# HBridge.net
KiCad netlist of a schematic drawn in Altium Designer
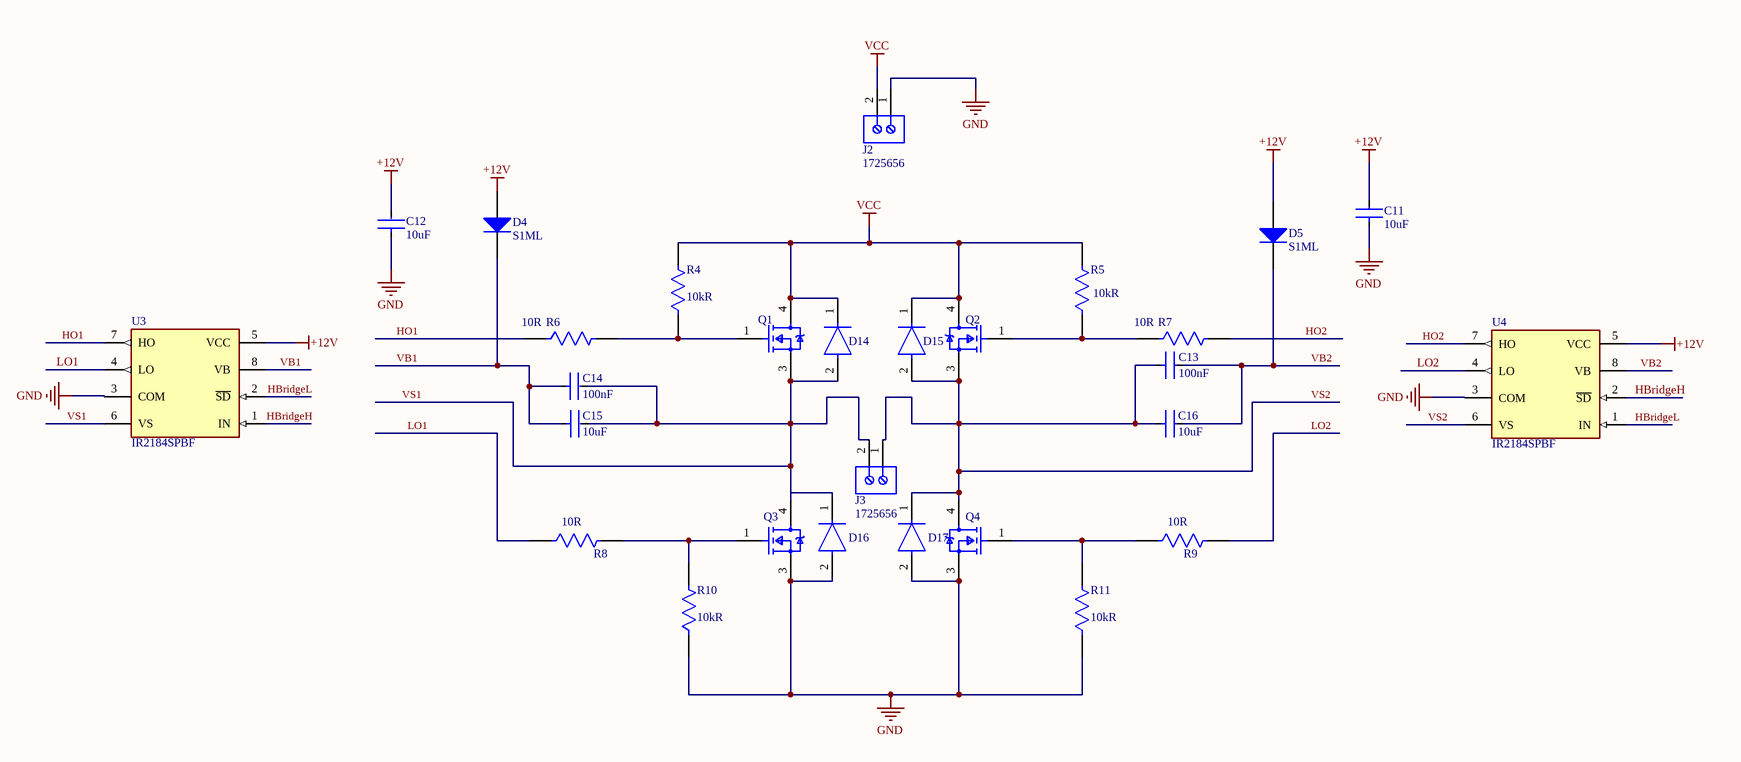
[diagram p0: HBridge.SchDoc]

(export (version "E")
  (design (tool "Eeschema 10.0.6"))
  (components
    (comp (ref "C11")
      (value "CL21A106KOQNNNE")
      (footprint "FP-CL21-IPC_B")
      (description "CL21 Series 0805 10uF 16V ±10% Tolerance X5R Multilayer Ceramic Chip Capacitor")
      (fields
        (field (name "VOLTAGE") "16V")
        (field (name "CAPACITANCE") "10uF")
        (field (name "TOLERANCE") "10%")
      )
      (libsource (lib "Altium Content Vault") (part "b4654b650e69147ec39a6b967a45e02"))
    )
    (comp (ref "C12")
      (value "CL21A106KOQNNNE")
      (footprint "FP-CL21-IPC_B")
      (description "CL21 Series 0805 10uF 16V ±10% Tolerance X5R Multilayer Ceramic Chip Capacitor")
      (fields
        (field (name "VOLTAGE") "16V")
        (field (name "CAPACITANCE") "10uF")
        (field (name "TOLERANCE") "10%")
      )
      (libsource (lib "Altium Content Vault") (part "b4654b650e69147ec39a6b967a45e02"))
    )
    (comp (ref "C13")
      (value "CL21B104KBCNNNC")
      (footprint "FP-CL21-IPC_C")
      (description "CL21 Series 0805 100nF 50V ±10% Tolerance X7R Multilayer Ceramic Chip Capacitor")
      (fields
        (field (name "TOLERANCE") "10%")
        (field (name "CAPACITANCE") "100nF")
        (field (name "VOLTAGE") "50V")
      )
      (libsource (lib "Altium Content Vault") (part "b4654b650e69147ec39a6b967a45e02"))
    )
    (comp (ref "C14")
      (value "CL21B104KBCNNNC")
      (footprint "FP-CL21-IPC_C")
      (description "CL21 Series 0805 100nF 50V ±10% Tolerance X7R Multilayer Ceramic Chip Capacitor")
      (fields
        (field (name "TOLERANCE") "10%")
        (field (name "CAPACITANCE") "100nF")
        (field (name "VOLTAGE") "50V")
      )
      (libsource (lib "Altium Content Vault") (part "b4654b650e69147ec39a6b967a45e02"))
    )
    (comp (ref "C15")
      (value "CL21A106KOQNNNE")
      (footprint "FP-CL21-IPC_B")
      (description "CL21 Series 0805 10uF 16V ±10% Tolerance X5R Multilayer Ceramic Chip Capacitor")
      (fields
        (field (name "VOLTAGE") "16V")
        (field (name "CAPACITANCE") "10uF")
        (field (name "TOLERANCE") "10%")
      )
      (libsource (lib "Altium Content Vault") (part "b4654b650e69147ec39a6b967a45e02"))
    )
    (comp (ref "C16")
      (value "CL21A106KOQNNNE")
      (footprint "FP-CL21-IPC_B")
      (description "CL21 Series 0805 10uF 16V ±10% Tolerance X5R Multilayer Ceramic Chip Capacitor")
      (fields
        (field (name "VOLTAGE") "16V")
        (field (name "CAPACITANCE") "10uF")
        (field (name "TOLERANCE") "10%")
      )
      (libsource (lib "Altium Content Vault") (part "b4654b650e69147ec39a6b967a45e02"))
    )
    (comp (ref "D4")
      (value "S1ML")
      (footprint "TWS-S1ML_V")
      (description "Rectifier, 1 A, 1.1 V, -55 to 175 degC, 2-Pin SMD, RoHS, Tape and Reel")
      (fields (field (name "MANUFACTURER") "Taiwan Semiconductor"))
      (libsource (lib "Altium Content Vault") (part "D-AK-2"))
    )
    (comp (ref "D5")
      (value "S1ML")
      (footprint "TWS-S1ML_V")
      (description "Rectifier, 1 A, 1.1 V, -55 to 175 degC, 2-Pin SMD, RoHS, Tape and Reel")
      (fields (field (name "MANUFACTURER") "Taiwan Semiconductor"))
      (libsource (lib "Altium Content Vault") (part "D-AK-2"))
    )
    (comp (ref "D14")
      (value "1N4148WQ-7-F")
      (footprint "FP-SOD123-MFG")
      (description "DIODE GEN PURP 100V 300MA SOD123")
      (fields
        (field (name "MANUFACTURER") "Diodes Inc.")
        (field (name "OCTOPART") "https://octopart.com/1n4148wq-7-f-diodes+inc.-34965875")
      )
      (libsource (lib "Altium Content Vault") (part "d7152d700b627762746794eb795d46e"))
    )
    (comp (ref "D15")
      (value "1N4148WQ-7-F")
      (footprint "FP-SOD123-MFG")
      (description "DIODE GEN PURP 100V 300MA SOD123")
      (fields
        (field (name "MANUFACTURER") "Diodes Inc.")
        (field (name "OCTOPART") "https://octopart.com/1n4148wq-7-f-diodes+inc.-34965875")
      )
      (libsource (lib "Altium Content Vault") (part "d7152d700b627762746794eb795d46e"))
    )
    (comp (ref "D16")
      (value "1N4148WQ-7-F")
      (footprint "FP-SOD123-MFG")
      (description "DIODE GEN PURP 100V 300MA SOD123")
      (fields
        (field (name "MANUFACTURER") "Diodes Inc.")
        (field (name "OCTOPART") "https://octopart.com/1n4148wq-7-f-diodes+inc.-34965875")
      )
      (libsource (lib "Altium Content Vault") (part "d7152d700b627762746794eb795d46e"))
    )
    (comp (ref "D17")
      (value "1N4148WQ-7-F")
      (footprint "FP-SOD123-MFG")
      (description "DIODE GEN PURP 100V 300MA SOD123")
      (fields
        (field (name "MANUFACTURER") "Diodes Inc.")
        (field (name "OCTOPART") "https://octopart.com/1n4148wq-7-f-diodes+inc.-34965875")
      )
      (libsource (lib "Altium Content Vault") (part "d7152d700b627762746794eb795d46e"))
    )
    (comp (ref "J2")
      (value "1725656")
      (footprint "PHOE-1725656-2")
      (description "Male Header, Pitch 2.54 mm, 1 x 2 Position, Height 9 mm, Tail Length 3.5 mm")
      (fields (field (name "MANUFACTURER") "Phoenix Contact"))
      (libsource (lib "Altium Content Vault") (part "CN-1P-F-TB2"))
    )
    (comp (ref "J3")
      (value "1725656")
      (footprint "PHOE-1725656-2")
      (description "Male Header, Pitch 2.54 mm, 1 x 2 Position, Height 9 mm, Tail Length 3.5 mm")
      (fields (field (name "MANUFACTURER") "Phoenix Contact"))
      (libsource (lib "Altium Content Vault") (part "CN-1P-F-TB2"))
    )
    (comp (ref "Q1")
      (value "IRLZ44NSTRLPBF")
      (footprint "FP-PG-TO263-3-MFG")
      (description "MOSFET N-CH 55V 47A D2PAK")
      (libsource (lib "Altium Content Vault") (part "cdf1c68f84cb049e5ebc85739c3fcf6"))
    )
    (comp (ref "Q2")
      (value "IRLZ44NSTRLPBF")
      (footprint "FP-PG-TO263-3-MFG")
      (description "MOSFET N-CH 55V 47A D2PAK")
      (libsource (lib "Altium Content Vault") (part "cdf1c68f84cb049e5ebc85739c3fcf6"))
    )
    (comp (ref "Q3")
      (value "IRLZ44NSTRLPBF")
      (footprint "FP-PG-TO263-3-MFG")
      (description "MOSFET N-CH 55V 47A D2PAK")
      (libsource (lib "Altium Content Vault") (part "cdf1c68f84cb049e5ebc85739c3fcf6"))
    )
    (comp (ref "Q4")
      (value "IRLZ44NSTRLPBF")
      (footprint "FP-PG-TO263-3-MFG")
      (description "MOSFET N-CH 55V 47A D2PAK")
      (libsource (lib "Altium Content Vault") (part "cdf1c68f84cb049e5ebc85739c3fcf6"))
    )
    (comp (ref "R4")
      (value "MCA1206MD1002DP500")
      (footprint "FP-MCA1206-IPC_B")
      (description "Res MC AT Professional Thin Film 1206 10kΩ 0.5% 0.4W ±25ppm/°C Molded Paper T/R")
      (fields (field (name "RESISTANCE") "10kR") (field (name "TOLERANCE") "0.5%"))
      (libsource (lib "Altium Content Vault") (part "1029c3af85768c4190bb7ad29bc67b5"))
    )
    (comp (ref "R5")
      (value "MCA1206MD1002DP500")
      (footprint "FP-MCA1206-IPC_B")
      (description "Res MC AT Professional Thin Film 1206 10kΩ 0.5% 0.4W ±25ppm/°C Molded Paper T/R")
      (fields (field (name "RESISTANCE") "10kR") (field (name "TOLERANCE") "0.5%"))
      (libsource (lib "Altium Content Vault") (part "1029c3af85768c4190bb7ad29bc67b5"))
    )
    (comp (ref "R6")
      (value "RMCF0805FG10R0")
      (footprint "FP-RMCF0805-IPC_B")
      (description "10Ω ±1% 0.125W 0805 Thick Film Chip Resistor AEC-Q200 compliant")
      (fields (field (name "RESISTANCE") "10R") (field (name "TOLERANCE") "1%"))
      (libsource (lib "Altium Content Vault") (part "1029c3af85768c4190bb7ad29bc67b5"))
    )
    (comp (ref "R7")
      (value "RMCF0805FG10R0")
      (footprint "FP-RMCF0805-IPC_B")
      (description "10Ω ±1% 0.125W 0805 Thick Film Chip Resistor AEC-Q200 compliant")
      (fields (field (name "RESISTANCE") "10R") (field (name "TOLERANCE") "1%"))
      (libsource (lib "Altium Content Vault") (part "1029c3af85768c4190bb7ad29bc67b5"))
    )
    (comp (ref "R8")
      (value "RMCF0805FG10R0")
      (footprint "FP-RMCF0805-IPC_B")
      (description "10Ω ±1% 0.125W 0805 Thick Film Chip Resistor AEC-Q200 compliant")
      (fields (field (name "RESISTANCE") "10R") (field (name "TOLERANCE") "1%"))
      (libsource (lib "Altium Content Vault") (part "1029c3af85768c4190bb7ad29bc67b5"))
    )
    (comp (ref "R9")
      (value "RMCF0805FG10R0")
      (footprint "FP-RMCF0805-IPC_B")
      (description "10Ω ±1% 0.125W 0805 Thick Film Chip Resistor AEC-Q200 compliant")
      (fields (field (name "RESISTANCE") "10R") (field (name "TOLERANCE") "1%"))
      (libsource (lib "Altium Content Vault") (part "1029c3af85768c4190bb7ad29bc67b5"))
    )
    (comp (ref "R10")
      (value "MCA1206MD1002DP500")
      (footprint "FP-MCA1206-IPC_B")
      (description "Res MC AT Professional Thin Film 1206 10kΩ 0.5% 0.4W ±25ppm/°C Molded Paper T/R")
      (fields (field (name "RESISTANCE") "10kR") (field (name "TOLERANCE") "0.5%"))
      (libsource (lib "Altium Content Vault") (part "1029c3af85768c4190bb7ad29bc67b5"))
    )
    (comp (ref "R11")
      (value "MCA1206MD1002DP500")
      (footprint "FP-MCA1206-IPC_B")
      (description "Res MC AT Professional Thin Film 1206 10kΩ 0.5% 0.4W ±25ppm/°C Molded Paper T/R")
      (fields (field (name "RESISTANCE") "10kR") (field (name "TOLERANCE") "0.5%"))
      (libsource (lib "Altium Content Vault") (part "1029c3af85768c4190bb7ad29bc67b5"))
    )
    (comp (ref "U3")
      (value "IR2184SPBF")
      (footprint "FP-PG-DSO-8-MFG")
      (description "IC GATE DRVR HALF-BRIDGE 8SOIC")
      (fields
        (field (name "MANUFACTURER") "Infineon")
        (field (name "OCTOPART") "https://octopart.com/ir2184spbf-infineon-65872954")
      )
      (libsource (lib "Altium Content Vault") (part "eadb07069977034a324a47831dd6aaa"))
    )
    (comp (ref "U4")
      (value "IR2184SPBF")
      (footprint "FP-PG-DSO-8-MFG")
      (description "IC GATE DRVR HALF-BRIDGE 8SOIC")
      (fields
        (field (name "MANUFACTURER") "Infineon")
        (field (name "OCTOPART") "https://octopart.com/ir2184spbf-infineon-65872954")
      )
      (libsource (lib "Altium Content Vault") (part "eadb07069977034a324a47831dd6aaa"))
    )
  )
  (nets
    (net (code "1") (name "+12V") (class "Default")
      (node (ref "C11") (pin "2") (pinfunction "2_2") (pintype "passive"))
      (node (ref "C12") (pin "2") (pinfunction "2_2") (pintype "passive"))
      (node (ref "D4") (pin "1") (pinfunction "A_1") (pintype "passive"))
      (node (ref "D5") (pin "1") (pinfunction "A_1") (pintype "passive"))
      (node (ref "U3") (pin "5") (pinfunction "VCC_5") (pintype "power_in"))
      (node (ref "U4") (pin "5") (pinfunction "VCC_5") (pintype "power_in"))
    )
    (net (code "2") (name "/HBridgeH") (class "Default")
      (node (ref "U3") (pin "1") (pinfunction "IN_1") (pintype "input"))
      (node (ref "U4") (pin "2") (pinfunction "~{SD}_2") (pintype "input"))
    )
    (net (code "3") (name "/HBridgeL") (class "Default")
      (node (ref "U3") (pin "2") (pinfunction "~{SD}_2") (pintype "input"))
      (node (ref "U4") (pin "1") (pinfunction "IN_1") (pintype "input"))
    )
    (net (code "4") (name "/HO1") (class "Default")
      (node (ref "R6") (pin "1") (pinfunction "1_1") (pintype "passive"))
      (node (ref "U3") (pin "7") (pinfunction "HO_7") (pintype "output"))
    )
    (net (code "5") (name "/HO2") (class "Default")
      (node (ref "R7") (pin "2") (pinfunction "2_2") (pintype "passive"))
      (node (ref "U4") (pin "7") (pinfunction "HO_7") (pintype "output"))
    )
    (net (code "6") (name "/LO1") (class "Default")
      (node (ref "R8") (pin "1") (pinfunction "1_1") (pintype "passive"))
      (node (ref "U3") (pin "4") (pinfunction "LO_4") (pintype "output"))
    )
    (net (code "7") (name "/LO2") (class "Default")
      (node (ref "R9") (pin "2") (pinfunction "2_2") (pintype "passive"))
      (node (ref "U4") (pin "4") (pinfunction "LO_4") (pintype "output"))
    )
    (net (code "8") (name "/VB1") (class "Default")
      (node (ref "C14") (pin "1") (pinfunction "1_1") (pintype "passive"))
      (node (ref "C15") (pin "1") (pinfunction "1_1") (pintype "passive"))
      (node (ref "D4") (pin "2") (pinfunction "K_2") (pintype "passive"))
      (node (ref "U3") (pin "8") (pinfunction "VB_8") (pintype "power_in"))
    )
    (net (code "9") (name "/VB2") (class "Default")
      (node (ref "C13") (pin "2") (pinfunction "2_2") (pintype "passive"))
      (node (ref "C16") (pin "2") (pinfunction "2_2") (pintype "passive"))
      (node (ref "D5") (pin "2") (pinfunction "K_2") (pintype "passive"))
      (node (ref "U4") (pin "8") (pinfunction "VB_8") (pintype "power_in"))
    )
    (net (code "10") (name "/VS1") (class "Default")
      (node (ref "C14") (pin "2") (pinfunction "2_2") (pintype "passive"))
      (node (ref "C15") (pin "2") (pinfunction "2_2") (pintype "passive"))
      (node (ref "D14") (pin "2") (pinfunction "A_2") (pintype "passive"))
      (node (ref "D16") (pin "1") (pinfunction "C_1") (pintype "passive"))
      (node (ref "J3") (pin "2") (pinfunction "2_2") (pintype "passive"))
      (node (ref "Q1") (pin "3") (pinfunction "S_3") (pintype "passive"))
      (node (ref "Q3") (pin "4") (pinfunction "D_4") (pintype "passive"))
      (node (ref "U3") (pin "6") (pinfunction "VS_6") (pintype "power_in"))
    )
    (net (code "11") (name "/VS2") (class "Default")
      (node (ref "C13") (pin "1") (pinfunction "1_1") (pintype "passive"))
      (node (ref "C16") (pin "1") (pinfunction "1_1") (pintype "passive"))
      (node (ref "D15") (pin "2") (pinfunction "A_2") (pintype "passive"))
      (node (ref "D17") (pin "1") (pinfunction "C_1") (pintype "passive"))
      (node (ref "J3") (pin "1") (pinfunction "1_1") (pintype "passive"))
      (node (ref "Q2") (pin "3") (pinfunction "S_3") (pintype "passive"))
      (node (ref "Q4") (pin "4") (pinfunction "D_4") (pintype "passive"))
      (node (ref "U4") (pin "6") (pinfunction "VS_6") (pintype "power_in"))
    )
    (net (code "12") (name "GND") (class "Default")
      (node (ref "C11") (pin "1") (pinfunction "1_1") (pintype "passive"))
      (node (ref "C12") (pin "1") (pinfunction "1_1") (pintype "passive"))
      (node (ref "D16") (pin "2") (pinfunction "A_2") (pintype "passive"))
      (node (ref "D17") (pin "2") (pinfunction "A_2") (pintype "passive"))
      (node (ref "J2") (pin "1") (pinfunction "1_1") (pintype "passive"))
      (node (ref "Q3") (pin "3") (pinfunction "S_3") (pintype "passive"))
      (node (ref "Q4") (pin "3") (pinfunction "S_3") (pintype "passive"))
      (node (ref "R10") (pin "1") (pinfunction "1_1") (pintype "passive"))
      (node (ref "R11") (pin "1") (pinfunction "1_1") (pintype "passive"))
      (node (ref "U3") (pin "3") (pinfunction "COM_3") (pintype "power_in"))
      (node (ref "U4") (pin "3") (pinfunction "COM_3") (pintype "power_in"))
    )
    (net (code "13") (name "Net-(Q1-G)") (class "Default")
      (node (ref "Q1") (pin "1") (pinfunction "G_1") (pintype "passive"))
      (node (ref "R4") (pin "1") (pinfunction "1_1") (pintype "passive"))
      (node (ref "R6") (pin "2") (pinfunction "2_2") (pintype "passive"))
    )
    (net (code "14") (name "Net-(Q2-G)") (class "Default")
      (node (ref "Q2") (pin "1") (pinfunction "G_1") (pintype "passive"))
      (node (ref "R5") (pin "1") (pinfunction "1_1") (pintype "passive"))
      (node (ref "R7") (pin "1") (pinfunction "1_1") (pintype "passive"))
    )
    (net (code "15") (name "Net-(Q3-G)") (class "Default")
      (node (ref "Q3") (pin "1") (pinfunction "G_1") (pintype "passive"))
      (node (ref "R10") (pin "2") (pinfunction "2_2") (pintype "passive"))
      (node (ref "R8") (pin "2") (pinfunction "2_2") (pintype "passive"))
    )
    (net (code "16") (name "Net-(Q4-G)") (class "Default")
      (node (ref "Q4") (pin "1") (pinfunction "G_1") (pintype "passive"))
      (node (ref "R11") (pin "2") (pinfunction "2_2") (pintype "passive"))
      (node (ref "R9") (pin "1") (pinfunction "1_1") (pintype "passive"))
    )
    (net (code "17") (name "VCC") (class "Default")
      (node (ref "D14") (pin "1") (pinfunction "C_1") (pintype "passive"))
      (node (ref "D15") (pin "1") (pinfunction "C_1") (pintype "passive"))
      (node (ref "J2") (pin "2") (pinfunction "2_2") (pintype "passive"))
      (node (ref "Q1") (pin "4") (pinfunction "D_4") (pintype "passive"))
      (node (ref "Q2") (pin "4") (pinfunction "D_4") (pintype "passive"))
      (node (ref "R4") (pin "2") (pinfunction "2_2") (pintype "passive"))
      (node (ref "R5") (pin "2") (pinfunction "2_2") (pintype "passive"))
    )
  )
)
